# MATRIX.net
KiCad netlist of a schematic drawn in Altium Designer
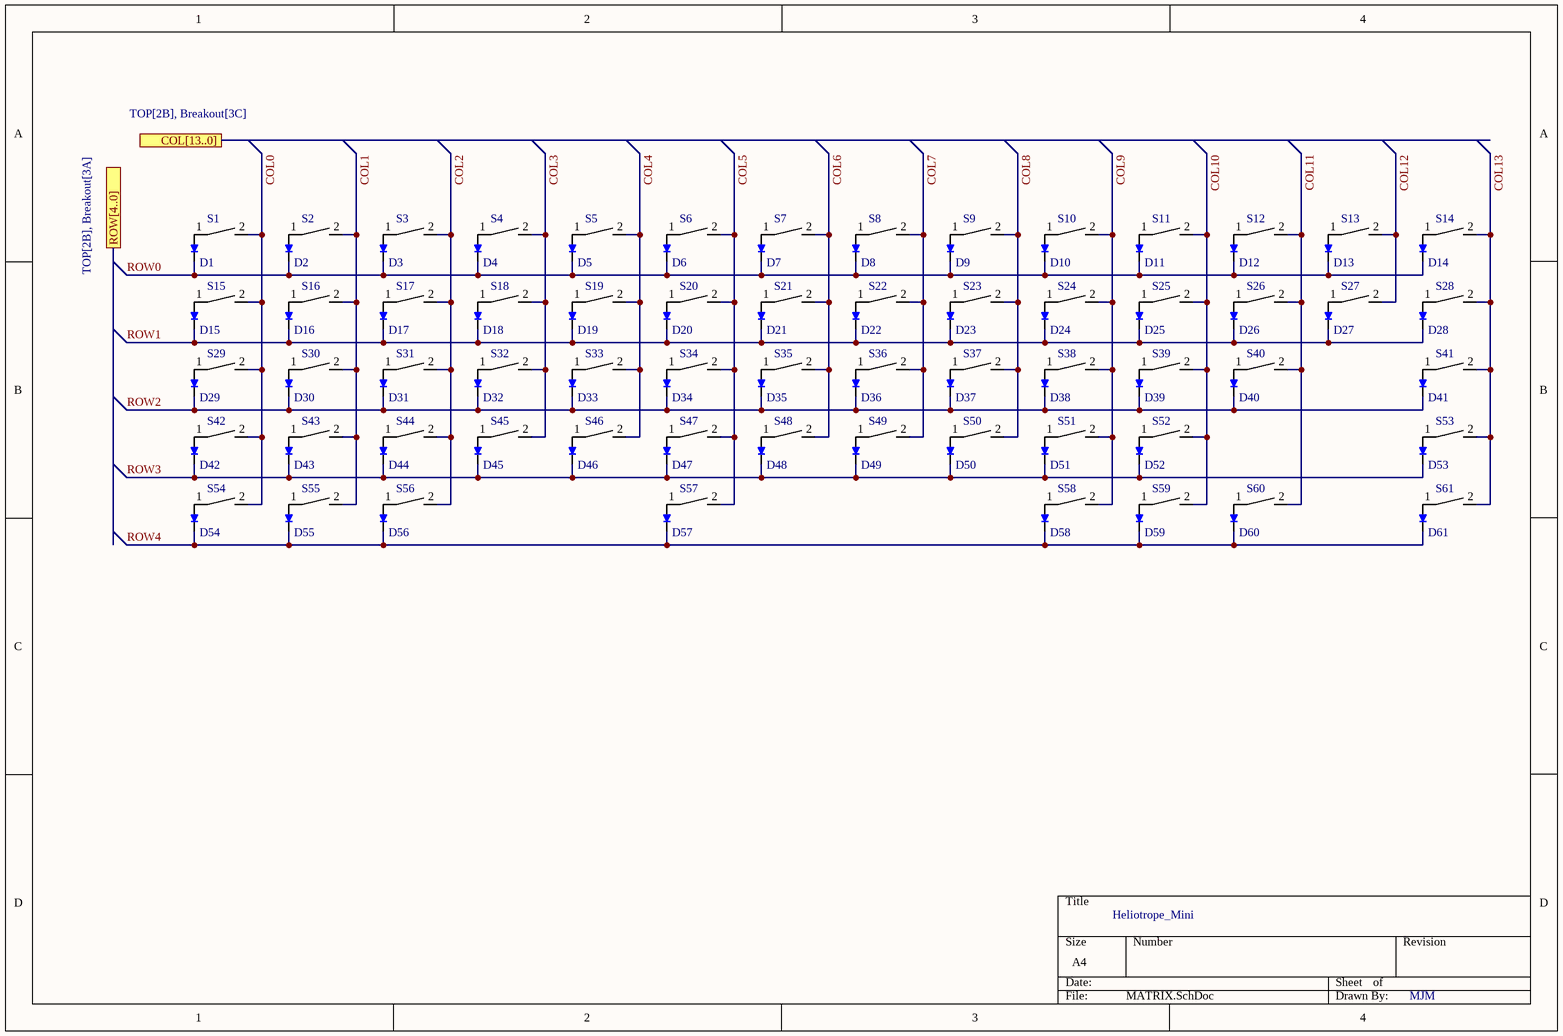
[diagram p0: MATRIX.SchDoc]

(export (version "E")
  (design (tool "Eeschema 10.0.6"))
  (components
    (comp (ref "D1")
      (value "RB520S30T5G")
      (footprint "ONSC-SOD-523-2-502-01_V")
      (description "RB520S30T5G - 30 V 200 mA Surface Mount Schottky Diode - SOD-523")
      (libsource (lib "Microcom Corporation") (part "ONSC-D-K1A2-2"))
    )
    (comp (ref "D2")
      (value "RB520S30T5G")
      (footprint "ONSC-SOD-523-2-502-01_V")
      (description "RB520S30T5G - 30 V 200 mA Surface Mount Schottky Diode - SOD-523")
      (libsource (lib "Microcom Corporation") (part "ONSC-D-K1A2-2"))
    )
    (comp (ref "D3")
      (value "RB520S30T5G")
      (footprint "ONSC-SOD-523-2-502-01_V")
      (description "RB520S30T5G - 30 V 200 mA Surface Mount Schottky Diode - SOD-523")
      (libsource (lib "Microcom Corporation") (part "ONSC-D-K1A2-2"))
    )
    (comp (ref "D4")
      (value "RB520S30T5G")
      (footprint "ONSC-SOD-523-2-502-01_V")
      (description "RB520S30T5G - 30 V 200 mA Surface Mount Schottky Diode - SOD-523")
      (libsource (lib "Microcom Corporation") (part "ONSC-D-K1A2-2"))
    )
    (comp (ref "D5")
      (value "RB520S30T5G")
      (footprint "ONSC-SOD-523-2-502-01_V")
      (description "RB520S30T5G - 30 V 200 mA Surface Mount Schottky Diode - SOD-523")
      (libsource (lib "Microcom Corporation") (part "ONSC-D-K1A2-2"))
    )
    (comp (ref "D6")
      (value "RB520S30T5G")
      (footprint "ONSC-SOD-523-2-502-01_V")
      (description "RB520S30T5G - 30 V 200 mA Surface Mount Schottky Diode - SOD-523")
      (libsource (lib "Microcom Corporation") (part "ONSC-D-K1A2-2"))
    )
    (comp (ref "D7")
      (value "RB520S30T5G")
      (footprint "ONSC-SOD-523-2-502-01_V")
      (description "RB520S30T5G - 30 V 200 mA Surface Mount Schottky Diode - SOD-523")
      (libsource (lib "Microcom Corporation") (part "ONSC-D-K1A2-2"))
    )
    (comp (ref "D8")
      (value "RB520S30T5G")
      (footprint "ONSC-SOD-523-2-502-01_V")
      (description "RB520S30T5G - 30 V 200 mA Surface Mount Schottky Diode - SOD-523")
      (libsource (lib "Microcom Corporation") (part "ONSC-D-K1A2-2"))
    )
    (comp (ref "D9")
      (value "RB520S30T5G")
      (footprint "ONSC-SOD-523-2-502-01_V")
      (description "RB520S30T5G - 30 V 200 mA Surface Mount Schottky Diode - SOD-523")
      (libsource (lib "Microcom Corporation") (part "ONSC-D-K1A2-2"))
    )
    (comp (ref "D10")
      (value "RB520S30T5G")
      (footprint "ONSC-SOD-523-2-502-01_V")
      (description "RB520S30T5G - 30 V 200 mA Surface Mount Schottky Diode - SOD-523")
      (libsource (lib "Microcom Corporation") (part "ONSC-D-K1A2-2"))
    )
    (comp (ref "D11")
      (value "RB520S30T5G")
      (footprint "ONSC-SOD-523-2-502-01_V")
      (description "RB520S30T5G - 30 V 200 mA Surface Mount Schottky Diode - SOD-523")
      (libsource (lib "Microcom Corporation") (part "ONSC-D-K1A2-2"))
    )
    (comp (ref "D12")
      (value "RB520S30T5G")
      (footprint "ONSC-SOD-523-2-502-01_V")
      (description "RB520S30T5G - 30 V 200 mA Surface Mount Schottky Diode - SOD-523")
      (libsource (lib "Microcom Corporation") (part "ONSC-D-K1A2-2"))
    )
    (comp (ref "D13")
      (value "RB520S30T5G")
      (footprint "ONSC-SOD-523-2-502-01_V")
      (description "RB520S30T5G - 30 V 200 mA Surface Mount Schottky Diode - SOD-523")
      (libsource (lib "Microcom Corporation") (part "ONSC-D-K1A2-2"))
    )
    (comp (ref "D14")
      (value "RB520S30T5G")
      (footprint "ONSC-SOD-523-2-502-01_V")
      (description "RB520S30T5G - 30 V 200 mA Surface Mount Schottky Diode - SOD-523")
      (libsource (lib "Microcom Corporation") (part "ONSC-D-K1A2-2"))
    )
    (comp (ref "D15")
      (value "RB520S30T5G")
      (footprint "ONSC-SOD-523-2-502-01_V")
      (description "RB520S30T5G - 30 V 200 mA Surface Mount Schottky Diode - SOD-523")
      (libsource (lib "Microcom Corporation") (part "ONSC-D-K1A2-2"))
    )
    (comp (ref "D16")
      (value "RB520S30T5G")
      (footprint "ONSC-SOD-523-2-502-01_V")
      (description "RB520S30T5G - 30 V 200 mA Surface Mount Schottky Diode - SOD-523")
      (libsource (lib "Microcom Corporation") (part "ONSC-D-K1A2-2"))
    )
    (comp (ref "D17")
      (value "RB520S30T5G")
      (footprint "ONSC-SOD-523-2-502-01_V")
      (description "RB520S30T5G - 30 V 200 mA Surface Mount Schottky Diode - SOD-523")
      (libsource (lib "Microcom Corporation") (part "ONSC-D-K1A2-2"))
    )
    (comp (ref "D18")
      (value "RB520S30T5G")
      (footprint "ONSC-SOD-523-2-502-01_V")
      (description "RB520S30T5G - 30 V 200 mA Surface Mount Schottky Diode - SOD-523")
      (libsource (lib "Microcom Corporation") (part "ONSC-D-K1A2-2"))
    )
    (comp (ref "D19")
      (value "RB520S30T5G")
      (footprint "ONSC-SOD-523-2-502-01_V")
      (description "RB520S30T5G - 30 V 200 mA Surface Mount Schottky Diode - SOD-523")
      (libsource (lib "Microcom Corporation") (part "ONSC-D-K1A2-2"))
    )
    (comp (ref "D20")
      (value "RB520S30T5G")
      (footprint "ONSC-SOD-523-2-502-01_V")
      (description "RB520S30T5G - 30 V 200 mA Surface Mount Schottky Diode - SOD-523")
      (libsource (lib "Microcom Corporation") (part "ONSC-D-K1A2-2"))
    )
    (comp (ref "D21")
      (value "RB520S30T5G")
      (footprint "ONSC-SOD-523-2-502-01_V")
      (description "RB520S30T5G - 30 V 200 mA Surface Mount Schottky Diode - SOD-523")
      (libsource (lib "Microcom Corporation") (part "ONSC-D-K1A2-2"))
    )
    (comp (ref "D22")
      (value "RB520S30T5G")
      (footprint "ONSC-SOD-523-2-502-01_V")
      (description "RB520S30T5G - 30 V 200 mA Surface Mount Schottky Diode - SOD-523")
      (libsource (lib "Microcom Corporation") (part "ONSC-D-K1A2-2"))
    )
    (comp (ref "D23")
      (value "RB520S30T5G")
      (footprint "ONSC-SOD-523-2-502-01_V")
      (description "RB520S30T5G - 30 V 200 mA Surface Mount Schottky Diode - SOD-523")
      (libsource (lib "Microcom Corporation") (part "ONSC-D-K1A2-2"))
    )
    (comp (ref "D24")
      (value "RB520S30T5G")
      (footprint "ONSC-SOD-523-2-502-01_V")
      (description "RB520S30T5G - 30 V 200 mA Surface Mount Schottky Diode - SOD-523")
      (libsource (lib "Microcom Corporation") (part "ONSC-D-K1A2-2"))
    )
    (comp (ref "D25")
      (value "RB520S30T5G")
      (footprint "ONSC-SOD-523-2-502-01_V")
      (description "RB520S30T5G - 30 V 200 mA Surface Mount Schottky Diode - SOD-523")
      (libsource (lib "Microcom Corporation") (part "ONSC-D-K1A2-2"))
    )
    (comp (ref "D26")
      (value "RB520S30T5G")
      (footprint "ONSC-SOD-523-2-502-01_V")
      (description "RB520S30T5G - 30 V 200 mA Surface Mount Schottky Diode - SOD-523")
      (libsource (lib "Microcom Corporation") (part "ONSC-D-K1A2-2"))
    )
    (comp (ref "D27")
      (value "RB520S30T5G")
      (footprint "ONSC-SOD-523-2-502-01_V")
      (description "RB520S30T5G - 30 V 200 mA Surface Mount Schottky Diode - SOD-523")
      (libsource (lib "Microcom Corporation") (part "ONSC-D-K1A2-2"))
    )
    (comp (ref "D28")
      (value "RB520S30T5G")
      (footprint "ONSC-SOD-523-2-502-01_V")
      (description "RB520S30T5G - 30 V 200 mA Surface Mount Schottky Diode - SOD-523")
      (libsource (lib "Microcom Corporation") (part "ONSC-D-K1A2-2"))
    )
    (comp (ref "D29")
      (value "RB520S30T5G")
      (footprint "ONSC-SOD-523-2-502-01_V")
      (description "RB520S30T5G - 30 V 200 mA Surface Mount Schottky Diode - SOD-523")
      (libsource (lib "Microcom Corporation") (part "ONSC-D-K1A2-2"))
    )
    (comp (ref "D30")
      (value "RB520S30T5G")
      (footprint "ONSC-SOD-523-2-502-01_V")
      (description "RB520S30T5G - 30 V 200 mA Surface Mount Schottky Diode - SOD-523")
      (libsource (lib "Microcom Corporation") (part "ONSC-D-K1A2-2"))
    )
    (comp (ref "D31")
      (value "RB520S30T5G")
      (footprint "ONSC-SOD-523-2-502-01_V")
      (description "RB520S30T5G - 30 V 200 mA Surface Mount Schottky Diode - SOD-523")
      (libsource (lib "Microcom Corporation") (part "ONSC-D-K1A2-2"))
    )
    (comp (ref "D32")
      (value "RB520S30T5G")
      (footprint "ONSC-SOD-523-2-502-01_V")
      (description "RB520S30T5G - 30 V 200 mA Surface Mount Schottky Diode - SOD-523")
      (libsource (lib "Microcom Corporation") (part "ONSC-D-K1A2-2"))
    )
    (comp (ref "D33")
      (value "RB520S30T5G")
      (footprint "ONSC-SOD-523-2-502-01_V")
      (description "RB520S30T5G - 30 V 200 mA Surface Mount Schottky Diode - SOD-523")
      (libsource (lib "Microcom Corporation") (part "ONSC-D-K1A2-2"))
    )
    (comp (ref "D34")
      (value "RB520S30T5G")
      (footprint "ONSC-SOD-523-2-502-01_V")
      (description "RB520S30T5G - 30 V 200 mA Surface Mount Schottky Diode - SOD-523")
      (libsource (lib "Microcom Corporation") (part "ONSC-D-K1A2-2"))
    )
    (comp (ref "D35")
      (value "RB520S30T5G")
      (footprint "ONSC-SOD-523-2-502-01_V")
      (description "RB520S30T5G - 30 V 200 mA Surface Mount Schottky Diode - SOD-523")
      (libsource (lib "Microcom Corporation") (part "ONSC-D-K1A2-2"))
    )
    (comp (ref "D36")
      (value "RB520S30T5G")
      (footprint "ONSC-SOD-523-2-502-01_V")
      (description "RB520S30T5G - 30 V 200 mA Surface Mount Schottky Diode - SOD-523")
      (libsource (lib "Microcom Corporation") (part "ONSC-D-K1A2-2"))
    )
    (comp (ref "D37")
      (value "RB520S30T5G")
      (footprint "ONSC-SOD-523-2-502-01_V")
      (description "RB520S30T5G - 30 V 200 mA Surface Mount Schottky Diode - SOD-523")
      (libsource (lib "Microcom Corporation") (part "ONSC-D-K1A2-2"))
    )
    (comp (ref "D38")
      (value "RB520S30T5G")
      (footprint "ONSC-SOD-523-2-502-01_V")
      (description "RB520S30T5G - 30 V 200 mA Surface Mount Schottky Diode - SOD-523")
      (libsource (lib "Microcom Corporation") (part "ONSC-D-K1A2-2"))
    )
    (comp (ref "D39")
      (value "RB520S30T5G")
      (footprint "ONSC-SOD-523-2-502-01_V")
      (description "RB520S30T5G - 30 V 200 mA Surface Mount Schottky Diode - SOD-523")
      (libsource (lib "Microcom Corporation") (part "ONSC-D-K1A2-2"))
    )
    (comp (ref "D40")
      (value "RB520S30T5G")
      (footprint "ONSC-SOD-523-2-502-01_V")
      (description "RB520S30T5G - 30 V 200 mA Surface Mount Schottky Diode - SOD-523")
      (libsource (lib "Microcom Corporation") (part "ONSC-D-K1A2-2"))
    )
    (comp (ref "D41")
      (value "RB520S30T5G")
      (footprint "ONSC-SOD-523-2-502-01_V")
      (description "RB520S30T5G - 30 V 200 mA Surface Mount Schottky Diode - SOD-523")
      (libsource (lib "Microcom Corporation") (part "ONSC-D-K1A2-2"))
    )
    (comp (ref "D42")
      (value "RB520S30T5G")
      (footprint "ONSC-SOD-523-2-502-01_V")
      (description "RB520S30T5G - 30 V 200 mA Surface Mount Schottky Diode - SOD-523")
      (libsource (lib "Microcom Corporation") (part "ONSC-D-K1A2-2"))
    )
    (comp (ref "D43")
      (value "RB520S30T5G")
      (footprint "ONSC-SOD-523-2-502-01_V")
      (description "RB520S30T5G - 30 V 200 mA Surface Mount Schottky Diode - SOD-523")
      (libsource (lib "Microcom Corporation") (part "ONSC-D-K1A2-2"))
    )
    (comp (ref "D44")
      (value "RB520S30T5G")
      (footprint "ONSC-SOD-523-2-502-01_V")
      (description "RB520S30T5G - 30 V 200 mA Surface Mount Schottky Diode - SOD-523")
      (libsource (lib "Microcom Corporation") (part "ONSC-D-K1A2-2"))
    )
    (comp (ref "D45")
      (value "RB520S30T5G")
      (footprint "ONSC-SOD-523-2-502-01_V")
      (description "RB520S30T5G - 30 V 200 mA Surface Mount Schottky Diode - SOD-523")
      (libsource (lib "Microcom Corporation") (part "ONSC-D-K1A2-2"))
    )
    (comp (ref "D46")
      (value "RB520S30T5G")
      (footprint "ONSC-SOD-523-2-502-01_V")
      (description "RB520S30T5G - 30 V 200 mA Surface Mount Schottky Diode - SOD-523")
      (libsource (lib "Microcom Corporation") (part "ONSC-D-K1A2-2"))
    )
    (comp (ref "D47")
      (value "RB520S30T5G")
      (footprint "ONSC-SOD-523-2-502-01_V")
      (description "RB520S30T5G - 30 V 200 mA Surface Mount Schottky Diode - SOD-523")
      (libsource (lib "Microcom Corporation") (part "ONSC-D-K1A2-2"))
    )
    (comp (ref "D48")
      (value "RB520S30T5G")
      (footprint "ONSC-SOD-523-2-502-01_V")
      (description "RB520S30T5G - 30 V 200 mA Surface Mount Schottky Diode - SOD-523")
      (libsource (lib "Microcom Corporation") (part "ONSC-D-K1A2-2"))
    )
    (comp (ref "D49")
      (value "RB520S30T5G")
      (footprint "ONSC-SOD-523-2-502-01_V")
      (description "RB520S30T5G - 30 V 200 mA Surface Mount Schottky Diode - SOD-523")
      (libsource (lib "Microcom Corporation") (part "ONSC-D-K1A2-2"))
    )
    (comp (ref "D50")
      (value "RB520S30T5G")
      (footprint "ONSC-SOD-523-2-502-01_V")
      (description "RB520S30T5G - 30 V 200 mA Surface Mount Schottky Diode - SOD-523")
      (libsource (lib "Microcom Corporation") (part "ONSC-D-K1A2-2"))
    )
    (comp (ref "D51")
      (value "RB520S30T5G")
      (footprint "ONSC-SOD-523-2-502-01_V")
      (description "RB520S30T5G - 30 V 200 mA Surface Mount Schottky Diode - SOD-523")
      (libsource (lib "Microcom Corporation") (part "ONSC-D-K1A2-2"))
    )
    (comp (ref "D52")
      (value "RB520S30T5G")
      (footprint "ONSC-SOD-523-2-502-01_V")
      (description "RB520S30T5G - 30 V 200 mA Surface Mount Schottky Diode - SOD-523")
      (libsource (lib "Microcom Corporation") (part "ONSC-D-K1A2-2"))
    )
    (comp (ref "D53")
      (value "RB520S30T5G")
      (footprint "ONSC-SOD-523-2-502-01_V")
      (description "RB520S30T5G - 30 V 200 mA Surface Mount Schottky Diode - SOD-523")
      (libsource (lib "Microcom Corporation") (part "ONSC-D-K1A2-2"))
    )
    (comp (ref "D54")
      (value "RB520S30T5G")
      (footprint "ONSC-SOD-523-2-502-01_V")
      (description "RB520S30T5G - 30 V 200 mA Surface Mount Schottky Diode - SOD-523")
      (libsource (lib "Microcom Corporation") (part "ONSC-D-K1A2-2"))
    )
    (comp (ref "D55")
      (value "RB520S30T5G")
      (footprint "ONSC-SOD-523-2-502-01_V")
      (description "RB520S30T5G - 30 V 200 mA Surface Mount Schottky Diode - SOD-523")
      (libsource (lib "Microcom Corporation") (part "ONSC-D-K1A2-2"))
    )
    (comp (ref "D56")
      (value "RB520S30T5G")
      (footprint "ONSC-SOD-523-2-502-01_V")
      (description "RB520S30T5G - 30 V 200 mA Surface Mount Schottky Diode - SOD-523")
      (libsource (lib "Microcom Corporation") (part "ONSC-D-K1A2-2"))
    )
    (comp (ref "D57")
      (value "RB520S30T5G")
      (footprint "ONSC-SOD-523-2-502-01_V")
      (description "RB520S30T5G - 30 V 200 mA Surface Mount Schottky Diode - SOD-523")
      (libsource (lib "Microcom Corporation") (part "ONSC-D-K1A2-2"))
    )
    (comp (ref "D58")
      (value "RB520S30T5G")
      (footprint "ONSC-SOD-523-2-502-01_V")
      (description "RB520S30T5G - 30 V 200 mA Surface Mount Schottky Diode - SOD-523")
      (libsource (lib "Microcom Corporation") (part "ONSC-D-K1A2-2"))
    )
    (comp (ref "D59")
      (value "RB520S30T5G")
      (footprint "ONSC-SOD-523-2-502-01_V")
      (description "RB520S30T5G - 30 V 200 mA Surface Mount Schottky Diode - SOD-523")
      (libsource (lib "Microcom Corporation") (part "ONSC-D-K1A2-2"))
    )
    (comp (ref "D60")
      (value "RB520S30T5G")
      (footprint "ONSC-SOD-523-2-502-01_V")
      (description "RB520S30T5G - 30 V 200 mA Surface Mount Schottky Diode - SOD-523")
      (libsource (lib "Microcom Corporation") (part "ONSC-D-K1A2-2"))
    )
    (comp (ref "D61")
      (value "RB520S30T5G")
      (footprint "ONSC-SOD-523-2-502-01_V")
      (description "RB520S30T5G - 30 V 200 mA Surface Mount Schottky Diode - SOD-523")
      (libsource (lib "Microcom Corporation") (part "ONSC-D-K1A2-2"))
    )
    (comp (ref "S1")
      (value "1U")
      (footprint "SW_PG151101S11")
      (description "Keyswitch 1U Cherry MX")
      (fields
        (field (name "BUYPART") "https://www.snapeda.com/parts/PG151101S11/Kailh/view-part/4218555/?ref=eda")
        (field (name "MP") "PG151101S11")
      )
      (libsource (lib "Microcom Corporation") (part "PG151101S11"))
    )
    (comp (ref "S2")
      (value "1U")
      (footprint "SW_PG151101S11")
      (description "Keyswitch 1U Cherry MX")
      (fields
        (field (name "BUYPART") "https://www.snapeda.com/parts/PG151101S11/Kailh/view-part/4218555/?ref=eda")
        (field (name "MP") "PG151101S11")
      )
      (libsource (lib "Microcom Corporation") (part "PG151101S11"))
    )
    (comp (ref "S3")
      (value "1U")
      (footprint "SW_PG151101S11")
      (description "Keyswitch 1U Cherry MX")
      (fields
        (field (name "BUYPART") "https://www.snapeda.com/parts/PG151101S11/Kailh/view-part/4218555/?ref=eda")
        (field (name "MP") "PG151101S11")
      )
      (libsource (lib "Microcom Corporation") (part "PG151101S11"))
    )
    (comp (ref "S4")
      (value "1U")
      (footprint "SW_PG151101S11")
      (description "Keyswitch 1U Cherry MX")
      (fields
        (field (name "BUYPART") "https://www.snapeda.com/parts/PG151101S11/Kailh/view-part/4218555/?ref=eda")
        (field (name "MP") "PG151101S11")
      )
      (libsource (lib "Microcom Corporation") (part "PG151101S11"))
    )
    (comp (ref "S5")
      (value "1U")
      (footprint "SW_PG151101S11")
      (description "Keyswitch 1U Cherry MX")
      (fields
        (field (name "BUYPART") "https://www.snapeda.com/parts/PG151101S11/Kailh/view-part/4218555/?ref=eda")
        (field (name "MP") "PG151101S11")
      )
      (libsource (lib "Microcom Corporation") (part "PG151101S11"))
    )
    (comp (ref "S6")
      (value "1U")
      (footprint "SW_PG151101S11")
      (description "Keyswitch 1U Cherry MX")
      (fields
        (field (name "BUYPART") "https://www.snapeda.com/parts/PG151101S11/Kailh/view-part/4218555/?ref=eda")
        (field (name "MP") "PG151101S11")
      )
      (libsource (lib "Microcom Corporation") (part "PG151101S11"))
    )
    (comp (ref "S7")
      (value "1U")
      (footprint "SW_PG151101S11")
      (description "Keyswitch 1U Cherry MX")
      (fields
        (field (name "BUYPART") "https://www.snapeda.com/parts/PG151101S11/Kailh/view-part/4218555/?ref=eda")
        (field (name "MP") "PG151101S11")
      )
      (libsource (lib "Microcom Corporation") (part "PG151101S11"))
    )
    (comp (ref "S8")
      (value "1U")
      (footprint "SW_PG151101S11")
      (description "Keyswitch 1U Cherry MX")
      (fields
        (field (name "BUYPART") "https://www.snapeda.com/parts/PG151101S11/Kailh/view-part/4218555/?ref=eda")
        (field (name "MP") "PG151101S11")
      )
      (libsource (lib "Microcom Corporation") (part "PG151101S11"))
    )
    (comp (ref "S9")
      (value "1U")
      (footprint "SW_PG151101S11")
      (description "Keyswitch 1U Cherry MX")
      (fields
        (field (name "BUYPART") "https://www.snapeda.com/parts/PG151101S11/Kailh/view-part/4218555/?ref=eda")
        (field (name "MP") "PG151101S11")
      )
      (libsource (lib "Microcom Corporation") (part "PG151101S11"))
    )
    (comp (ref "S10")
      (value "1U")
      (footprint "SW_PG151101S11")
      (description "Keyswitch 1U Cherry MX")
      (fields
        (field (name "BUYPART") "https://www.snapeda.com/parts/PG151101S11/Kailh/view-part/4218555/?ref=eda")
        (field (name "MP") "PG151101S11")
      )
      (libsource (lib "Microcom Corporation") (part "PG151101S11"))
    )
    (comp (ref "S11")
      (value "1U")
      (footprint "SW_PG151101S11")
      (description "Keyswitch 1U Cherry MX")
      (fields
        (field (name "BUYPART") "https://www.snapeda.com/parts/PG151101S11/Kailh/view-part/4218555/?ref=eda")
        (field (name "MP") "PG151101S11")
      )
      (libsource (lib "Microcom Corporation") (part "PG151101S11"))
    )
    (comp (ref "S12")
      (value "1U")
      (footprint "SW_PG151101S11")
      (description "Keyswitch 1U Cherry MX")
      (fields
        (field (name "BUYPART") "https://www.snapeda.com/parts/PG151101S11/Kailh/view-part/4218555/?ref=eda")
        (field (name "MP") "PG151101S11")
      )
      (libsource (lib "Microcom Corporation") (part "PG151101S11"))
    )
    (comp (ref "S13")
      (value "1U")
      (footprint "SW_PG151101S11")
      (description "Keyswitch 1U Cherry MX")
      (fields
        (field (name "BUYPART") "https://www.snapeda.com/parts/PG151101S11/Kailh/view-part/4218555/?ref=eda")
        (field (name "MP") "PG151101S11")
      )
      (libsource (lib "Microcom Corporation") (part "PG151101S11"))
    )
    (comp (ref "S14")
      (value "2U")
      (footprint "SW_PG151101S11")
      (description "Keyswitch 2U Cherry MX")
      (fields
        (field (name "BUYPART") "https://www.snapeda.com/parts/PG151101S11/Kailh/view-part/4218555/?ref=eda")
        (field (name "MF") "Kailh")
      )
      (libsource (lib "Microcom Corporation") (part "PG151101S11"))
    )
    (comp (ref "S15")
      (value "1U")
      (footprint "SW_PG151101S11")
      (description "Keyswitch 1U Cherry MX")
      (fields
        (field (name "BUYPART") "https://www.snapeda.com/parts/PG151101S11/Kailh/view-part/4218555/?ref=eda")
        (field (name "MP") "PG151101S11")
      )
      (libsource (lib "Microcom Corporation") (part "PG151101S11"))
    )
    (comp (ref "S16")
      (value "1U")
      (footprint "SW_PG151101S11")
      (description "Keyswitch 1U Cherry MX")
      (fields
        (field (name "BUYPART") "https://www.snapeda.com/parts/PG151101S11/Kailh/view-part/4218555/?ref=eda")
        (field (name "MP") "PG151101S11")
      )
      (libsource (lib "Microcom Corporation") (part "PG151101S11"))
    )
    (comp (ref "S17")
      (value "1U")
      (footprint "SW_PG151101S11")
      (description "Keyswitch 1U Cherry MX")
      (fields
        (field (name "BUYPART") "https://www.snapeda.com/parts/PG151101S11/Kailh/view-part/4218555/?ref=eda")
        (field (name "MP") "PG151101S11")
      )
      (libsource (lib "Microcom Corporation") (part "PG151101S11"))
    )
    (comp (ref "S18")
      (value "1U")
      (footprint "SW_PG151101S11")
      (description "Keyswitch 1U Cherry MX")
      (fields
        (field (name "BUYPART") "https://www.snapeda.com/parts/PG151101S11/Kailh/view-part/4218555/?ref=eda")
        (field (name "MP") "PG151101S11")
      )
      (libsource (lib "Microcom Corporation") (part "PG151101S11"))
    )
    (comp (ref "S19")
      (value "1U")
      (footprint "SW_PG151101S11")
      (description "Keyswitch 1U Cherry MX")
      (fields
        (field (name "BUYPART") "https://www.snapeda.com/parts/PG151101S11/Kailh/view-part/4218555/?ref=eda")
        (field (name "MP") "PG151101S11")
      )
      (libsource (lib "Microcom Corporation") (part "PG151101S11"))
    )
    (comp (ref "S20")
      (value "1U")
      (footprint "SW_PG151101S11")
      (description "Keyswitch 1U Cherry MX")
      (fields
        (field (name "BUYPART") "https://www.snapeda.com/parts/PG151101S11/Kailh/view-part/4218555/?ref=eda")
        (field (name "MP") "PG151101S11")
      )
      (libsource (lib "Microcom Corporation") (part "PG151101S11"))
    )
    (comp (ref "S21")
      (value "1U")
      (footprint "SW_PG151101S11")
      (description "Keyswitch 1U Cherry MX")
      (fields
        (field (name "BUYPART") "https://www.snapeda.com/parts/PG151101S11/Kailh/view-part/4218555/?ref=eda")
        (field (name "MP") "PG151101S11")
      )
      (libsource (lib "Microcom Corporation") (part "PG151101S11"))
    )
    (comp (ref "S22")
      (value "1U")
      (footprint "SW_PG151101S11")
      (description "Keyswitch 1U Cherry MX")
      (fields
        (field (name "BUYPART") "https://www.snapeda.com/parts/PG151101S11/Kailh/view-part/4218555/?ref=eda")
        (field (name "MP") "PG151101S11")
      )
      (libsource (lib "Microcom Corporation") (part "PG151101S11"))
    )
    (comp (ref "S23")
      (value "1U")
      (footprint "SW_PG151101S11")
      (description "Keyswitch 1U Cherry MX")
      (fields
        (field (name "BUYPART") "https://www.snapeda.com/parts/PG151101S11/Kailh/view-part/4218555/?ref=eda")
        (field (name "MP") "PG151101S11")
      )
      (libsource (lib "Microcom Corporation") (part "PG151101S11"))
    )
    (comp (ref "S24")
      (value "1U")
      (footprint "SW_PG151101S11")
      (description "Keyswitch 1U Cherry MX")
      (fields
        (field (name "BUYPART") "https://www.snapeda.com/parts/PG151101S11/Kailh/view-part/4218555/?ref=eda")
        (field (name "MP") "PG151101S11")
      )
      (libsource (lib "Microcom Corporation") (part "PG151101S11"))
    )
    (comp (ref "S25")
      (value "1U")
      (footprint "SW_PG151101S11")
      (description "Keyswitch 1U Cherry MX")
      (fields
        (field (name "BUYPART") "https://www.snapeda.com/parts/PG151101S11/Kailh/view-part/4218555/?ref=eda")
        (field (name "MP") "PG151101S11")
      )
      (libsource (lib "Microcom Corporation") (part "PG151101S11"))
    )
    (comp (ref "S26")
      (value "1U")
      (footprint "SW_PG151101S11")
      (description "Keyswitch 1U Cherry MX")
      (fields
        (field (name "BUYPART") "https://www.snapeda.com/parts/PG151101S11/Kailh/view-part/4218555/?ref=eda")
        (field (name "MP") "PG151101S11")
      )
      (libsource (lib "Microcom Corporation") (part "PG151101S11"))
    )
    (comp (ref "S27")
      (value "1U")
      (footprint "SW_PG151101S11")
      (description "Keyswitch 1U Cherry MX")
      (fields
        (field (name "BUYPART") "https://www.snapeda.com/parts/PG151101S11/Kailh/view-part/4218555/?ref=eda")
        (field (name "MP") "PG151101S11")
      )
      (libsource (lib "Microcom Corporation") (part "PG151101S11"))
    )
    (comp (ref "S28")
      (value "1U")
      (footprint "SW_PG151101S11")
      (description "Keyswitch 1U Cherry MX")
      (fields
        (field (name "BUYPART") "https://www.snapeda.com/parts/PG151101S11/Kailh/view-part/4218555/?ref=eda")
        (field (name "MP") "PG151101S11")
      )
      (libsource (lib "Microcom Corporation") (part "PG151101S11"))
    )
    (comp (ref "S29")
      (value "1U")
      (footprint "SW_PG151101S11")
      (description "Keyswitch 1U Cherry MX")
      (fields
        (field (name "BUYPART") "https://www.snapeda.com/parts/PG151101S11/Kailh/view-part/4218555/?ref=eda")
        (field (name "MP") "PG151101S11")
      )
      (libsource (lib "Microcom Corporation") (part "PG151101S11"))
    )
    (comp (ref "S30")
      (value "1U")
      (footprint "SW_PG151101S11")
      (description "Keyswitch 1U Cherry MX")
      (fields
        (field (name "BUYPART") "https://www.snapeda.com/parts/PG151101S11/Kailh/view-part/4218555/?ref=eda")
        (field (name "MP") "PG151101S11")
      )
      (libsource (lib "Microcom Corporation") (part "PG151101S11"))
    )
    (comp (ref "S31")
      (value "1U")
      (footprint "SW_PG151101S11")
      (description "Keyswitch 1U Cherry MX")
      (fields
        (field (name "BUYPART") "https://www.snapeda.com/parts/PG151101S11/Kailh/view-part/4218555/?ref=eda")
        (field (name "MP") "PG151101S11")
      )
      (libsource (lib "Microcom Corporation") (part "PG151101S11"))
    )
    (comp (ref "S32")
      (value "1U")
      (footprint "SW_PG151101S11")
      (description "Keyswitch 1U Cherry MX")
      (fields
        (field (name "BUYPART") "https://www.snapeda.com/parts/PG151101S11/Kailh/view-part/4218555/?ref=eda")
        (field (name "MP") "PG151101S11")
      )
      (libsource (lib "Microcom Corporation") (part "PG151101S11"))
    )
    (comp (ref "S33")
      (value "1U")
      (footprint "SW_PG151101S11")
      (description "Keyswitch 1U Cherry MX")
      (fields
        (field (name "BUYPART") "https://www.snapeda.com/parts/PG151101S11/Kailh/view-part/4218555/?ref=eda")
        (field (name "MP") "PG151101S11")
      )
      (libsource (lib "Microcom Corporation") (part "PG151101S11"))
    )
    (comp (ref "S34")
      (value "1U")
      (footprint "SW_PG151101S11")
      (description "Keyswitch 1U Cherry MX")
      (fields
        (field (name "BUYPART") "https://www.snapeda.com/parts/PG151101S11/Kailh/view-part/4218555/?ref=eda")
        (field (name "MP") "PG151101S11")
      )
      (libsource (lib "Microcom Corporation") (part "PG151101S11"))
    )
    (comp (ref "S35")
      (value "1U")
      (footprint "SW_PG151101S11")
      (description "Keyswitch 1U Cherry MX")
      (fields
        (field (name "BUYPART") "https://www.snapeda.com/parts/PG151101S11/Kailh/view-part/4218555/?ref=eda")
        (field (name "MP") "PG151101S11")
      )
      (libsource (lib "Microcom Corporation") (part "PG151101S11"))
    )
    (comp (ref "S36")
      (value "1U")
      (footprint "SW_PG151101S11")
      (description "Keyswitch 1U Cherry MX")
      (fields
        (field (name "BUYPART") "https://www.snapeda.com/parts/PG151101S11/Kailh/view-part/4218555/?ref=eda")
        (field (name "MP") "PG151101S11")
      )
      (libsource (lib "Microcom Corporation") (part "PG151101S11"))
    )
    (comp (ref "S37")
      (value "1U")
      (footprint "SW_PG151101S11")
      (description "Keyswitch 1U Cherry MX")
      (fields
        (field (name "BUYPART") "https://www.snapeda.com/parts/PG151101S11/Kailh/view-part/4218555/?ref=eda")
        (field (name "MP") "PG151101S11")
      )
      (libsource (lib "Microcom Corporation") (part "PG151101S11"))
    )
    (comp (ref "S38")
      (value "1U")
      (footprint "SW_PG151101S11")
      (description "Keyswitch 1U Cherry MX")
      (fields
        (field (name "BUYPART") "https://www.snapeda.com/parts/PG151101S11/Kailh/view-part/4218555/?ref=eda")
        (field (name "MP") "PG151101S11")
      )
      (libsource (lib "Microcom Corporation") (part "PG151101S11"))
    )
    (comp (ref "S39")
      (value "1U")
      (footprint "SW_PG151101S11")
      (description "Keyswitch 1U Cherry MX")
      (fields
        (field (name "BUYPART") "https://www.snapeda.com/parts/PG151101S11/Kailh/view-part/4218555/?ref=eda")
        (field (name "MP") "PG151101S11")
      )
      (libsource (lib "Microcom Corporation") (part "PG151101S11"))
    )
    (comp (ref "S40")
      (value "1U")
      (footprint "SW_PG151101S11")
      (description "Keyswitch 1U Cherry MX")
      (fields
        (field (name "BUYPART") "https://www.snapeda.com/parts/PG151101S11/Kailh/view-part/4218555/?ref=eda")
        (field (name "MP") "PG151101S11")
      )
      (libsource (lib "Microcom Corporation") (part "PG151101S11"))
    )
    (comp (ref "S41")
      (value "2U")
      (footprint "SW_PG151101S11")
      (description "Keyswitch 2U Cherry MX")
      (fields
        (field (name "BUYPART") "https://www.snapeda.com/parts/PG151101S11/Kailh/view-part/4218555/?ref=eda")
        (field (name "MF") "Kailh")
      )
      (libsource (lib "Microcom Corporation") (part "PG151101S11"))
    )
    (comp (ref "S42")
      (value "2U")
      (footprint "SW_PG151101S11")
      (description "Keyswitch 2U Cherry MX")
      (fields
        (field (name "BUYPART") "https://www.snapeda.com/parts/PG151101S11/Kailh/view-part/4218555/?ref=eda")
        (field (name "MF") "Kailh")
      )
      (libsource (lib "Microcom Corporation") (part "PG151101S11"))
    )
    (comp (ref "S43")
      (value "1U")
      (footprint "SW_PG151101S11")
      (description "Keyswitch 1U Cherry MX")
      (fields
        (field (name "BUYPART") "https://www.snapeda.com/parts/PG151101S11/Kailh/view-part/4218555/?ref=eda")
        (field (name "MP") "PG151101S11")
      )
      (libsource (lib "Microcom Corporation") (part "PG151101S11"))
    )
    (comp (ref "S44")
      (value "1U")
      (footprint "SW_PG151101S11")
      (description "Keyswitch 1U Cherry MX")
      (fields
        (field (name "BUYPART") "https://www.snapeda.com/parts/PG151101S11/Kailh/view-part/4218555/?ref=eda")
        (field (name "MP") "PG151101S11")
      )
      (libsource (lib "Microcom Corporation") (part "PG151101S11"))
    )
    (comp (ref "S45")
      (value "1U")
      (footprint "SW_PG151101S11")
      (description "Keyswitch 1U Cherry MX")
      (fields
        (field (name "BUYPART") "https://www.snapeda.com/parts/PG151101S11/Kailh/view-part/4218555/?ref=eda")
        (field (name "MP") "PG151101S11")
      )
      (libsource (lib "Microcom Corporation") (part "PG151101S11"))
    )
    (comp (ref "S46")
      (value "1U")
      (footprint "SW_PG151101S11")
      (description "Keyswitch 1U Cherry MX")
      (fields
        (field (name "BUYPART") "https://www.snapeda.com/parts/PG151101S11/Kailh/view-part/4218555/?ref=eda")
        (field (name "MP") "PG151101S11")
      )
      (libsource (lib "Microcom Corporation") (part "PG151101S11"))
    )
    (comp (ref "S47")
      (value "1U")
      (footprint "SW_PG151101S11")
      (description "Keyswitch 1U Cherry MX")
      (fields
        (field (name "BUYPART") "https://www.snapeda.com/parts/PG151101S11/Kailh/view-part/4218555/?ref=eda")
        (field (name "MP") "PG151101S11")
      )
      (libsource (lib "Microcom Corporation") (part "PG151101S11"))
    )
    (comp (ref "S48")
      (value "1U")
      (footprint "SW_PG151101S11")
      (description "Keyswitch 1U Cherry MX")
      (fields
        (field (name "BUYPART") "https://www.snapeda.com/parts/PG151101S11/Kailh/view-part/4218555/?ref=eda")
        (field (name "MP") "PG151101S11")
      )
      (libsource (lib "Microcom Corporation") (part "PG151101S11"))
    )
    (comp (ref "S49")
      (value "1U")
      (footprint "SW_PG151101S11")
      (description "Keyswitch 1U Cherry MX")
      (fields
        (field (name "BUYPART") "https://www.snapeda.com/parts/PG151101S11/Kailh/view-part/4218555/?ref=eda")
        (field (name "MP") "PG151101S11")
      )
      (libsource (lib "Microcom Corporation") (part "PG151101S11"))
    )
    (comp (ref "S50")
      (value "1U")
      (footprint "SW_PG151101S11")
      (description "Keyswitch 1U Cherry MX")
      (fields
        (field (name "BUYPART") "https://www.snapeda.com/parts/PG151101S11/Kailh/view-part/4218555/?ref=eda")
        (field (name "MP") "PG151101S11")
      )
      (libsource (lib "Microcom Corporation") (part "PG151101S11"))
    )
    (comp (ref "S51")
      (value "1U")
      (footprint "SW_PG151101S11")
      (description "Keyswitch 1U Cherry MX")
      (fields
        (field (name "BUYPART") "https://www.snapeda.com/parts/PG151101S11/Kailh/view-part/4218555/?ref=eda")
        (field (name "MP") "PG151101S11")
      )
      (libsource (lib "Microcom Corporation") (part "PG151101S11"))
    )
    (comp (ref "S52")
      (value "1U")
      (footprint "SW_PG151101S11")
      (description "Keyswitch 1U Cherry MX")
      (fields
        (field (name "BUYPART") "https://www.snapeda.com/parts/PG151101S11/Kailh/view-part/4218555/?ref=eda")
        (field (name "MP") "PG151101S11")
      )
      (libsource (lib "Microcom Corporation") (part "PG151101S11"))
    )
    (comp (ref "S53")
      (value "2U")
      (footprint "SW_PG151101S11")
      (description "Keyswitch 2U Cherry MX")
      (fields
        (field (name "BUYPART") "https://www.snapeda.com/parts/PG151101S11/Kailh/view-part/4218555/?ref=eda")
        (field (name "MF") "Kailh")
      )
      (libsource (lib "Microcom Corporation") (part "PG151101S11"))
    )
    (comp (ref "S54")
      (value "1U")
      (footprint "SW_PG151101S11")
      (description "Keyswitch 1U Cherry MX")
      (fields
        (field (name "BUYPART") "https://www.snapeda.com/parts/PG151101S11/Kailh/view-part/4218555/?ref=eda")
        (field (name "MP") "PG151101S11")
      )
      (libsource (lib "Microcom Corporation") (part "PG151101S11"))
    )
    (comp (ref "S55")
      (value "1U")
      (footprint "SW_PG151101S11")
      (description "Keyswitch 1U Cherry MX")
      (fields
        (field (name "BUYPART") "https://www.snapeda.com/parts/PG151101S11/Kailh/view-part/4218555/?ref=eda")
        (field (name "MP") "PG151101S11")
      )
      (libsource (lib "Microcom Corporation") (part "PG151101S11"))
    )
    (comp (ref "S56")
      (value "1U")
      (footprint "SW_PG151101S11")
      (description "Keyswitch 1U Cherry MX")
      (fields
        (field (name "BUYPART") "https://www.snapeda.com/parts/PG151101S11/Kailh/view-part/4218555/?ref=eda")
        (field (name "MP") "PG151101S11")
      )
      (libsource (lib "Microcom Corporation") (part "PG151101S11"))
    )
    (comp (ref "S57")
      (value "6.25U")
      (footprint "SW_PG151101S11")
      (description "Keyswitch 6.25U Cherry MX")
      (fields (field (name "MF") "Kailh") (field (name "MP") "PG151101S11"))
      (libsource (lib "Microcom Corporation") (part "PG151101S11"))
    )
    (comp (ref "S58")
      (value "1U")
      (footprint "SW_PG151101S11")
      (description "Keyswitch 1U Cherry MX")
      (fields
        (field (name "BUYPART") "https://www.snapeda.com/parts/PG151101S11/Kailh/view-part/4218555/?ref=eda")
        (field (name "MP") "PG151101S11")
      )
      (libsource (lib "Microcom Corporation") (part "PG151101S11"))
    )
    (comp (ref "S59")
      (value "1U")
      (footprint "SW_PG151101S11")
      (description "Keyswitch 1U Cherry MX")
      (fields
        (field (name "BUYPART") "https://www.snapeda.com/parts/PG151101S11/Kailh/view-part/4218555/?ref=eda")
        (field (name "MP") "PG151101S11")
      )
      (libsource (lib "Microcom Corporation") (part "PG151101S11"))
    )
    (comp (ref "S60")
      (value "1U")
      (footprint "SW_PG151101S11")
      (description "Keyswitch 1U Cherry MX")
      (fields
        (field (name "BUYPART") "https://www.snapeda.com/parts/PG151101S11/Kailh/view-part/4218555/?ref=eda")
        (field (name "MP") "PG151101S11")
      )
      (libsource (lib "Microcom Corporation") (part "PG151101S11"))
    )
    (comp (ref "S61")
      (value "1U")
      (footprint "SW_PG151101S11")
      (description "Keyswitch 1U Cherry MX")
      (fields
        (field (name "BUYPART") "https://www.snapeda.com/parts/PG151101S11/Kailh/view-part/4218555/?ref=eda")
        (field (name "MP") "PG151101S11")
      )
      (libsource (lib "Microcom Corporation") (part "PG151101S11"))
    )
  )
  (nets
    (net (code "1") (name "/COL0") (class "Default")
      (node (ref "S1") (pin "2") (pinfunction "2_2") (pintype "passive"))
      (node (ref "S15") (pin "2") (pinfunction "2_2") (pintype "passive"))
      (node (ref "S29") (pin "2") (pinfunction "2_2") (pintype "passive"))
      (node (ref "S42") (pin "2") (pinfunction "2_2") (pintype "passive"))
      (node (ref "S54") (pin "2") (pinfunction "2_2") (pintype "passive"))
    )
    (net (code "2") (name "/COL1") (class "Default")
      (node (ref "S16") (pin "2") (pinfunction "2_2") (pintype "passive"))
      (node (ref "S2") (pin "2") (pinfunction "2_2") (pintype "passive"))
      (node (ref "S30") (pin "2") (pinfunction "2_2") (pintype "passive"))
      (node (ref "S43") (pin "2") (pinfunction "2_2") (pintype "passive"))
      (node (ref "S55") (pin "2") (pinfunction "2_2") (pintype "passive"))
    )
    (net (code "3") (name "/COL2") (class "Default")
      (node (ref "S17") (pin "2") (pinfunction "2_2") (pintype "passive"))
      (node (ref "S3") (pin "2") (pinfunction "2_2") (pintype "passive"))
      (node (ref "S31") (pin "2") (pinfunction "2_2") (pintype "passive"))
      (node (ref "S44") (pin "2") (pinfunction "2_2") (pintype "passive"))
      (node (ref "S56") (pin "2") (pinfunction "2_2") (pintype "passive"))
    )
    (net (code "4") (name "/COL3") (class "Default")
      (node (ref "S18") (pin "2") (pinfunction "2_2") (pintype "passive"))
      (node (ref "S32") (pin "2") (pinfunction "2_2") (pintype "passive"))
      (node (ref "S4") (pin "2") (pinfunction "2_2") (pintype "passive"))
      (node (ref "S45") (pin "2") (pinfunction "2_2") (pintype "passive"))
    )
    (net (code "5") (name "/COL4") (class "Default")
      (node (ref "S19") (pin "2") (pinfunction "2_2") (pintype "passive"))
      (node (ref "S33") (pin "2") (pinfunction "2_2") (pintype "passive"))
      (node (ref "S46") (pin "2") (pinfunction "2_2") (pintype "passive"))
      (node (ref "S5") (pin "2") (pinfunction "2_2") (pintype "passive"))
    )
    (net (code "6") (name "/COL5") (class "Default")
      (node (ref "S20") (pin "2") (pinfunction "2_2") (pintype "passive"))
      (node (ref "S34") (pin "2") (pinfunction "2_2") (pintype "passive"))
      (node (ref "S47") (pin "2") (pinfunction "2_2") (pintype "passive"))
      (node (ref "S57") (pin "2") (pinfunction "2_2") (pintype "passive"))
      (node (ref "S6") (pin "2") (pinfunction "2_2") (pintype "passive"))
    )
    (net (code "7") (name "/COL6") (class "Default")
      (node (ref "S21") (pin "2") (pinfunction "2_2") (pintype "passive"))
      (node (ref "S35") (pin "2") (pinfunction "2_2") (pintype "passive"))
      (node (ref "S48") (pin "2") (pinfunction "2_2") (pintype "passive"))
      (node (ref "S7") (pin "2") (pinfunction "2_2") (pintype "passive"))
    )
    (net (code "8") (name "/COL7") (class "Default")
      (node (ref "S22") (pin "2") (pinfunction "2_2") (pintype "passive"))
      (node (ref "S36") (pin "2") (pinfunction "2_2") (pintype "passive"))
      (node (ref "S49") (pin "2") (pinfunction "2_2") (pintype "passive"))
      (node (ref "S8") (pin "2") (pinfunction "2_2") (pintype "passive"))
    )
    (net (code "9") (name "/COL8") (class "Default")
      (node (ref "S23") (pin "2") (pinfunction "2_2") (pintype "passive"))
      (node (ref "S37") (pin "2") (pinfunction "2_2") (pintype "passive"))
      (node (ref "S50") (pin "2") (pinfunction "2_2") (pintype "passive"))
      (node (ref "S9") (pin "2") (pinfunction "2_2") (pintype "passive"))
    )
    (net (code "10") (name "/COL9") (class "Default")
      (node (ref "S10") (pin "2") (pinfunction "2_2") (pintype "passive"))
      (node (ref "S24") (pin "2") (pinfunction "2_2") (pintype "passive"))
      (node (ref "S38") (pin "2") (pinfunction "2_2") (pintype "passive"))
      (node (ref "S51") (pin "2") (pinfunction "2_2") (pintype "passive"))
      (node (ref "S58") (pin "2") (pinfunction "2_2") (pintype "passive"))
    )
    (net (code "11") (name "/COL10") (class "Default")
      (node (ref "S11") (pin "2") (pinfunction "2_2") (pintype "passive"))
      (node (ref "S25") (pin "2") (pinfunction "2_2") (pintype "passive"))
      (node (ref "S39") (pin "2") (pinfunction "2_2") (pintype "passive"))
      (node (ref "S52") (pin "2") (pinfunction "2_2") (pintype "passive"))
      (node (ref "S59") (pin "2") (pinfunction "2_2") (pintype "passive"))
    )
    (net (code "12") (name "/COL11") (class "Default")
      (node (ref "S12") (pin "2") (pinfunction "2_2") (pintype "passive"))
      (node (ref "S26") (pin "2") (pinfunction "2_2") (pintype "passive"))
      (node (ref "S40") (pin "2") (pinfunction "2_2") (pintype "passive"))
      (node (ref "S60") (pin "2") (pinfunction "2_2") (pintype "passive"))
    )
    (net (code "13") (name "/COL12") (class "Default")
      (node (ref "S13") (pin "2") (pinfunction "2_2") (pintype "passive"))
      (node (ref "S27") (pin "2") (pinfunction "2_2") (pintype "passive"))
    )
    (net (code "14") (name "/COL13") (class "Default")
      (node (ref "S14") (pin "2") (pinfunction "2_2") (pintype "passive"))
      (node (ref "S28") (pin "2") (pinfunction "2_2") (pintype "passive"))
      (node (ref "S41") (pin "2") (pinfunction "2_2") (pintype "passive"))
      (node (ref "S53") (pin "2") (pinfunction "2_2") (pintype "passive"))
      (node (ref "S61") (pin "2") (pinfunction "2_2") (pintype "passive"))
    )
    (net (code "16") (name "/ROW0") (class "Default")
      (node (ref "D1") (pin "1") (pinfunction "K_1") (pintype "passive"))
      (node (ref "D10") (pin "1") (pinfunction "K_1") (pintype "passive"))
      (node (ref "D11") (pin "1") (pinfunction "K_1") (pintype "passive"))
      (node (ref "D12") (pin "1") (pinfunction "K_1") (pintype "passive"))
      (node (ref "D13") (pin "1") (pinfunction "K_1") (pintype "passive"))
      (node (ref "D14") (pin "1") (pinfunction "K_1") (pintype "passive"))
      (node (ref "D2") (pin "1") (pinfunction "K_1") (pintype "passive"))
      (node (ref "D3") (pin "1") (pinfunction "K_1") (pintype "passive"))
      (node (ref "D4") (pin "1") (pinfunction "K_1") (pintype "passive"))
      (node (ref "D5") (pin "1") (pinfunction "K_1") (pintype "passive"))
      (node (ref "D6") (pin "1") (pinfunction "K_1") (pintype "passive"))
      (node (ref "D7") (pin "1") (pinfunction "K_1") (pintype "passive"))
      (node (ref "D8") (pin "1") (pinfunction "K_1") (pintype "passive"))
      (node (ref "D9") (pin "1") (pinfunction "K_1") (pintype "passive"))
    )
    (net (code "17") (name "/ROW1") (class "Default")
      (node (ref "D15") (pin "1") (pinfunction "K_1") (pintype "passive"))
      (node (ref "D16") (pin "1") (pinfunction "K_1") (pintype "passive"))
      (node (ref "D17") (pin "1") (pinfunction "K_1") (pintype "passive"))
      (node (ref "D18") (pin "1") (pinfunction "K_1") (pintype "passive"))
      (node (ref "D19") (pin "1") (pinfunction "K_1") (pintype "passive"))
      (node (ref "D20") (pin "1") (pinfunction "K_1") (pintype "passive"))
      (node (ref "D21") (pin "1") (pinfunction "K_1") (pintype "passive"))
      (node (ref "D22") (pin "1") (pinfunction "K_1") (pintype "passive"))
      (node (ref "D23") (pin "1") (pinfunction "K_1") (pintype "passive"))
      (node (ref "D24") (pin "1") (pinfunction "K_1") (pintype "passive"))
      (node (ref "D25") (pin "1") (pinfunction "K_1") (pintype "passive"))
      (node (ref "D26") (pin "1") (pinfunction "K_1") (pintype "passive"))
      (node (ref "D27") (pin "1") (pinfunction "K_1") (pintype "passive"))
      (node (ref "D28") (pin "1") (pinfunction "K_1") (pintype "passive"))
    )
    (net (code "18") (name "/ROW2") (class "Default")
      (node (ref "D29") (pin "1") (pinfunction "K_1") (pintype "passive"))
      (node (ref "D30") (pin "1") (pinfunction "K_1") (pintype "passive"))
      (node (ref "D31") (pin "1") (pinfunction "K_1") (pintype "passive"))
      (node (ref "D32") (pin "1") (pinfunction "K_1") (pintype "passive"))
      (node (ref "D33") (pin "1") (pinfunction "K_1") (pintype "passive"))
      (node (ref "D34") (pin "1") (pinfunction "K_1") (pintype "passive"))
      (node (ref "D35") (pin "1") (pinfunction "K_1") (pintype "passive"))
      (node (ref "D36") (pin "1") (pinfunction "K_1") (pintype "passive"))
      (node (ref "D37") (pin "1") (pinfunction "K_1") (pintype "passive"))
      (node (ref "D38") (pin "1") (pinfunction "K_1") (pintype "passive"))
      (node (ref "D39") (pin "1") (pinfunction "K_1") (pintype "passive"))
      (node (ref "D40") (pin "1") (pinfunction "K_1") (pintype "passive"))
      (node (ref "D41") (pin "1") (pinfunction "K_1") (pintype "passive"))
    )
    (net (code "19") (name "/ROW3") (class "Default")
      (node (ref "D42") (pin "1") (pinfunction "K_1") (pintype "passive"))
      (node (ref "D43") (pin "1") (pinfunction "K_1") (pintype "passive"))
      (node (ref "D44") (pin "1") (pinfunction "K_1") (pintype "passive"))
      (node (ref "D45") (pin "1") (pinfunction "K_1") (pintype "passive"))
      (node (ref "D46") (pin "1") (pinfunction "K_1") (pintype "passive"))
      (node (ref "D47") (pin "1") (pinfunction "K_1") (pintype "passive"))
      (node (ref "D48") (pin "1") (pinfunction "K_1") (pintype "passive"))
      (node (ref "D49") (pin "1") (pinfunction "K_1") (pintype "passive"))
      (node (ref "D50") (pin "1") (pinfunction "K_1") (pintype "passive"))
      (node (ref "D51") (pin "1") (pinfunction "K_1") (pintype "passive"))
      (node (ref "D52") (pin "1") (pinfunction "K_1") (pintype "passive"))
      (node (ref "D53") (pin "1") (pinfunction "K_1") (pintype "passive"))
    )
    (net (code "20") (name "/ROW4") (class "Default")
      (node (ref "D54") (pin "1") (pinfunction "K_1") (pintype "passive"))
      (node (ref "D55") (pin "1") (pinfunction "K_1") (pintype "passive"))
      (node (ref "D56") (pin "1") (pinfunction "K_1") (pintype "passive"))
      (node (ref "D57") (pin "1") (pinfunction "K_1") (pintype "passive"))
      (node (ref "D58") (pin "1") (pinfunction "K_1") (pintype "passive"))
      (node (ref "D59") (pin "1") (pinfunction "K_1") (pintype "passive"))
      (node (ref "D60") (pin "1") (pinfunction "K_1") (pintype "passive"))
      (node (ref "D61") (pin "1") (pinfunction "K_1") (pintype "passive"))
    )
    (net (code "22") (name "Net-(D1-A)") (class "Default")
      (node (ref "D1") (pin "2") (pinfunction "A_2") (pintype "passive"))
      (node (ref "S1") (pin "1") (pinfunction "1_1") (pintype "passive"))
    )
    (net (code "23") (name "Net-(D2-A)") (class "Default")
      (node (ref "D2") (pin "2") (pinfunction "A_2") (pintype "passive"))
      (node (ref "S2") (pin "1") (pinfunction "1_1") (pintype "passive"))
    )
    (net (code "24") (name "Net-(D3-A)") (class "Default")
      (node (ref "D3") (pin "2") (pinfunction "A_2") (pintype "passive"))
      (node (ref "S3") (pin "1") (pinfunction "1_1") (pintype "passive"))
    )
    (net (code "25") (name "Net-(D4-A)") (class "Default")
      (node (ref "D4") (pin "2") (pinfunction "A_2") (pintype "passive"))
      (node (ref "S4") (pin "1") (pinfunction "1_1") (pintype "passive"))
    )
    (net (code "26") (name "Net-(D5-A)") (class "Default")
      (node (ref "D5") (pin "2") (pinfunction "A_2") (pintype "passive"))
      (node (ref "S5") (pin "1") (pinfunction "1_1") (pintype "passive"))
    )
    (net (code "27") (name "Net-(D6-A)") (class "Default")
      (node (ref "D6") (pin "2") (pinfunction "A_2") (pintype "passive"))
      (node (ref "S6") (pin "1") (pinfunction "1_1") (pintype "passive"))
    )
    (net (code "28") (name "Net-(D7-A)") (class "Default")
      (node (ref "D7") (pin "2") (pinfunction "A_2") (pintype "passive"))
      (node (ref "S7") (pin "1") (pinfunction "1_1") (pintype "passive"))
    )
    (net (code "29") (name "Net-(D8-A)") (class "Default")
      (node (ref "D8") (pin "2") (pinfunction "A_2") (pintype "passive"))
      (node (ref "S8") (pin "1") (pinfunction "1_1") (pintype "passive"))
    )
    (net (code "30") (name "Net-(D9-A)") (class "Default")
      (node (ref "D9") (pin "2") (pinfunction "A_2") (pintype "passive"))
      (node (ref "S9") (pin "1") (pinfunction "1_1") (pintype "passive"))
    )
    (net (code "31") (name "Net-(D10-A)") (class "Default")
      (node (ref "D10") (pin "2") (pinfunction "A_2") (pintype "passive"))
      (node (ref "S10") (pin "1") (pinfunction "1_1") (pintype "passive"))
    )
    (net (code "32") (name "Net-(D11-A)") (class "Default")
      (node (ref "D11") (pin "2") (pinfunction "A_2") (pintype "passive"))
      (node (ref "S11") (pin "1") (pinfunction "1_1") (pintype "passive"))
    )
    (net (code "33") (name "Net-(D12-A)") (class "Default")
      (node (ref "D12") (pin "2") (pinfunction "A_2") (pintype "passive"))
      (node (ref "S12") (pin "1") (pinfunction "1_1") (pintype "passive"))
    )
    (net (code "34") (name "Net-(D13-A)") (class "Default")
      (node (ref "D13") (pin "2") (pinfunction "A_2") (pintype "passive"))
      (node (ref "S13") (pin "1") (pinfunction "1_1") (pintype "passive"))
    )
    (net (code "35") (name "Net-(D14-A)") (class "Default")
      (node (ref "D14") (pin "2") (pinfunction "A_2") (pintype "passive"))
      (node (ref "S14") (pin "1") (pinfunction "1_1") (pintype "passive"))
    )
    (net (code "36") (name "Net-(D15-A)") (class "Default")
      (node (ref "D15") (pin "2") (pinfunction "A_2") (pintype "passive"))
      (node (ref "S15") (pin "1") (pinfunction "1_1") (pintype "passive"))
    )
    (net (code "37") (name "Net-(D16-A)") (class "Default")
      (node (ref "D16") (pin "2") (pinfunction "A_2") (pintype "passive"))
      (node (ref "S16") (pin "1") (pinfunction "1_1") (pintype "passive"))
    )
    (net (code "38") (name "Net-(D17-A)") (class "Default")
      (node (ref "D17") (pin "2") (pinfunction "A_2") (pintype "passive"))
      (node (ref "S17") (pin "1") (pinfunction "1_1") (pintype "passive"))
    )
    (net (code "39") (name "Net-(D18-A)") (class "Default")
      (node (ref "D18") (pin "2") (pinfunction "A_2") (pintype "passive"))
      (node (ref "S18") (pin "1") (pinfunction "1_1") (pintype "passive"))
    )
    (net (code "40") (name "Net-(D19-A)") (class "Default")
      (node (ref "D19") (pin "2") (pinfunction "A_2") (pintype "passive"))
      (node (ref "S19") (pin "1") (pinfunction "1_1") (pintype "passive"))
    )
    (net (code "41") (name "Net-(D20-A)") (class "Default")
      (node (ref "D20") (pin "2") (pinfunction "A_2") (pintype "passive"))
      (node (ref "S20") (pin "1") (pinfunction "1_1") (pintype "passive"))
    )
    (net (code "42") (name "Net-(D21-A)") (class "Default")
      (node (ref "D21") (pin "2") (pinfunction "A_2") (pintype "passive"))
      (node (ref "S21") (pin "1") (pinfunction "1_1") (pintype "passive"))
    )
    (net (code "43") (name "Net-(D22-A)") (class "Default")
      (node (ref "D22") (pin "2") (pinfunction "A_2") (pintype "passive"))
      (node (ref "S22") (pin "1") (pinfunction "1_1") (pintype "passive"))
    )
    (net (code "44") (name "Net-(D23-A)") (class "Default")
      (node (ref "D23") (pin "2") (pinfunction "A_2") (pintype "passive"))
      (node (ref "S23") (pin "1") (pinfunction "1_1") (pintype "passive"))
    )
    (net (code "45") (name "Net-(D24-A)") (class "Default")
      (node (ref "D24") (pin "2") (pinfunction "A_2") (pintype "passive"))
      (node (ref "S24") (pin "1") (pinfunction "1_1") (pintype "passive"))
    )
    (net (code "46") (name "Net-(D25-A)") (class "Default")
      (node (ref "D25") (pin "2") (pinfunction "A_2") (pintype "passive"))
      (node (ref "S25") (pin "1") (pinfunction "1_1") (pintype "passive"))
    )
    (net (code "47") (name "Net-(D26-A)") (class "Default")
      (node (ref "D26") (pin "2") (pinfunction "A_2") (pintype "passive"))
      (node (ref "S26") (pin "1") (pinfunction "1_1") (pintype "passive"))
    )
    (net (code "48") (name "Net-(D27-A)") (class "Default")
      (node (ref "D27") (pin "2") (pinfunction "A_2") (pintype "passive"))
      (node (ref "S27") (pin "1") (pinfunction "1_1") (pintype "passive"))
    )
    (net (code "49") (name "Net-(D28-A)") (class "Default")
      (node (ref "D28") (pin "2") (pinfunction "A_2") (pintype "passive"))
      (node (ref "S28") (pin "1") (pinfunction "1_1") (pintype "passive"))
    )
    (net (code "50") (name "Net-(D29-A)") (class "Default")
      (node (ref "D29") (pin "2") (pinfunction "A_2") (pintype "passive"))
      (node (ref "S29") (pin "1") (pinfunction "1_1") (pintype "passive"))
    )
    (net (code "51") (name "Net-(D30-A)") (class "Default")
      (node (ref "D30") (pin "2") (pinfunction "A_2") (pintype "passive"))
      (node (ref "S30") (pin "1") (pinfunction "1_1") (pintype "passive"))
    )
    (net (code "52") (name "Net-(D31-A)") (class "Default")
      (node (ref "D31") (pin "2") (pinfunction "A_2") (pintype "passive"))
      (node (ref "S31") (pin "1") (pinfunction "1_1") (pintype "passive"))
    )
    (net (code "53") (name "Net-(D32-A)") (class "Default")
      (node (ref "D32") (pin "2") (pinfunction "A_2") (pintype "passive"))
      (node (ref "S32") (pin "1") (pinfunction "1_1") (pintype "passive"))
    )
    (net (code "54") (name "Net-(D33-A)") (class "Default")
      (node (ref "D33") (pin "2") (pinfunction "A_2") (pintype "passive"))
      (node (ref "S33") (pin "1") (pinfunction "1_1") (pintype "passive"))
    )
    (net (code "55") (name "Net-(D34-A)") (class "Default")
      (node (ref "D34") (pin "2") (pinfunction "A_2") (pintype "passive"))
      (node (ref "S34") (pin "1") (pinfunction "1_1") (pintype "passive"))
    )
    (net (code "56") (name "Net-(D35-A)") (class "Default")
      (node (ref "D35") (pin "2") (pinfunction "A_2") (pintype "passive"))
      (node (ref "S35") (pin "1") (pinfunction "1_1") (pintype "passive"))
    )
    (net (code "57") (name "Net-(D36-A)") (class "Default")
      (node (ref "D36") (pin "2") (pinfunction "A_2") (pintype "passive"))
      (node (ref "S36") (pin "1") (pinfunction "1_1") (pintype "passive"))
    )
    (net (code "58") (name "Net-(D37-A)") (class "Default")
      (node (ref "D37") (pin "2") (pinfunction "A_2") (pintype "passive"))
      (node (ref "S37") (pin "1") (pinfunction "1_1") (pintype "passive"))
    )
    (net (code "59") (name "Net-(D38-A)") (class "Default")
      (node (ref "D38") (pin "2") (pinfunction "A_2") (pintype "passive"))
      (node (ref "S38") (pin "1") (pinfunction "1_1") (pintype "passive"))
    )
    (net (code "60") (name "Net-(D39-A)") (class "Default")
      (node (ref "D39") (pin "2") (pinfunction "A_2") (pintype "passive"))
      (node (ref "S39") (pin "1") (pinfunction "1_1") (pintype "passive"))
    )
    (net (code "61") (name "Net-(D40-A)") (class "Default")
      (node (ref "D40") (pin "2") (pinfunction "A_2") (pintype "passive"))
      (node (ref "S40") (pin "1") (pinfunction "1_1") (pintype "passive"))
    )
    (net (code "62") (name "Net-(D41-A)") (class "Default")
      (node (ref "D41") (pin "2") (pinfunction "A_2") (pintype "passive"))
      (node (ref "S41") (pin "1") (pinfunction "1_1") (pintype "passive"))
    )
    (net (code "63") (name "Net-(D42-A)") (class "Default")
      (node (ref "D42") (pin "2") (pinfunction "A_2") (pintype "passive"))
      (node (ref "S42") (pin "1") (pinfunction "1_1") (pintype "passive"))
    )
    (net (code "64") (name "Net-(D43-A)") (class "Default")
      (node (ref "D43") (pin "2") (pinfunction "A_2") (pintype "passive"))
      (node (ref "S43") (pin "1") (pinfunction "1_1") (pintype "passive"))
    )
    (net (code "65") (name "Net-(D44-A)") (class "Default")
      (node (ref "D44") (pin "2") (pinfunction "A_2") (pintype "passive"))
      (node (ref "S44") (pin "1") (pinfunction "1_1") (pintype "passive"))
    )
    (net (code "66") (name "Net-(D45-A)") (class "Default")
      (node (ref "D45") (pin "2") (pinfunction "A_2") (pintype "passive"))
      (node (ref "S45") (pin "1") (pinfunction "1_1") (pintype "passive"))
    )
    (net (code "67") (name "Net-(D46-A)") (class "Default")
      (node (ref "D46") (pin "2") (pinfunction "A_2") (pintype "passive"))
      (node (ref "S46") (pin "1") (pinfunction "1_1") (pintype "passive"))
    )
    (net (code "68") (name "Net-(D47-A)") (class "Default")
      (node (ref "D47") (pin "2") (pinfunction "A_2") (pintype "passive"))
      (node (ref "S47") (pin "1") (pinfunction "1_1") (pintype "passive"))
    )
    (net (code "69") (name "Net-(D48-A)") (class "Default")
      (node (ref "D48") (pin "2") (pinfunction "A_2") (pintype "passive"))
      (node (ref "S48") (pin "1") (pinfunction "1_1") (pintype "passive"))
    )
    (net (code "70") (name "Net-(D49-A)") (class "Default")
      (node (ref "D49") (pin "2") (pinfunction "A_2") (pintype "passive"))
      (node (ref "S49") (pin "1") (pinfunction "1_1") (pintype "passive"))
    )
    (net (code "71") (name "Net-(D50-A)") (class "Default")
      (node (ref "D50") (pin "2") (pinfunction "A_2") (pintype "passive"))
      (node (ref "S50") (pin "1") (pinfunction "1_1") (pintype "passive"))
    )
    (net (code "72") (name "Net-(D51-A)") (class "Default")
      (node (ref "D51") (pin "2") (pinfunction "A_2") (pintype "passive"))
      (node (ref "S51") (pin "1") (pinfunction "1_1") (pintype "passive"))
    )
    (net (code "73") (name "Net-(D52-A)") (class "Default")
      (node (ref "D52") (pin "2") (pinfunction "A_2") (pintype "passive"))
      (node (ref "S52") (pin "1") (pinfunction "1_1") (pintype "passive"))
    )
    (net (code "74") (name "Net-(D53-A)") (class "Default")
      (node (ref "D53") (pin "2") (pinfunction "A_2") (pintype "passive"))
      (node (ref "S53") (pin "1") (pinfunction "1_1") (pintype "passive"))
    )
    (net (code "75") (name "Net-(D54-A)") (class "Default")
      (node (ref "D54") (pin "2") (pinfunction "A_2") (pintype "passive"))
      (node (ref "S54") (pin "1") (pinfunction "1_1") (pintype "passive"))
    )
    (net (code "76") (name "Net-(D55-A)") (class "Default")
      (node (ref "D55") (pin "2") (pinfunction "A_2") (pintype "passive"))
      (node (ref "S55") (pin "1") (pinfunction "1_1") (pintype "passive"))
    )
    (net (code "77") (name "Net-(D56-A)") (class "Default")
      (node (ref "D56") (pin "2") (pinfunction "A_2") (pintype "passive"))
      (node (ref "S56") (pin "1") (pinfunction "1_1") (pintype "passive"))
    )
    (net (code "78") (name "Net-(D57-A)") (class "Default")
      (node (ref "D57") (pin "2") (pinfunction "A_2") (pintype "passive"))
      (node (ref "S57") (pin "1") (pinfunction "1_1") (pintype "passive"))
    )
    (net (code "79") (name "Net-(D58-A)") (class "Default")
      (node (ref "D58") (pin "2") (pinfunction "A_2") (pintype "passive"))
      (node (ref "S58") (pin "1") (pinfunction "1_1") (pintype "passive"))
    )
    (net (code "80") (name "Net-(D59-A)") (class "Default")
      (node (ref "D59") (pin "2") (pinfunction "A_2") (pintype "passive"))
      (node (ref "S59") (pin "1") (pinfunction "1_1") (pintype "passive"))
    )
    (net (code "81") (name "Net-(D60-A)") (class "Default")
      (node (ref "D60") (pin "2") (pinfunction "A_2") (pintype "passive"))
      (node (ref "S60") (pin "1") (pinfunction "1_1") (pintype "passive"))
    )
    (net (code "82") (name "Net-(D61-A)") (class "Default")
      (node (ref "D61") (pin "2") (pinfunction "A_2") (pintype "passive"))
      (node (ref "S61") (pin "1") (pinfunction "1_1") (pintype "passive"))
    )
  )
)
